# SCH_NFC-Card-Brendon_2024-10-28.net
KiCad netlist of a schematic drawn in EasyEDA
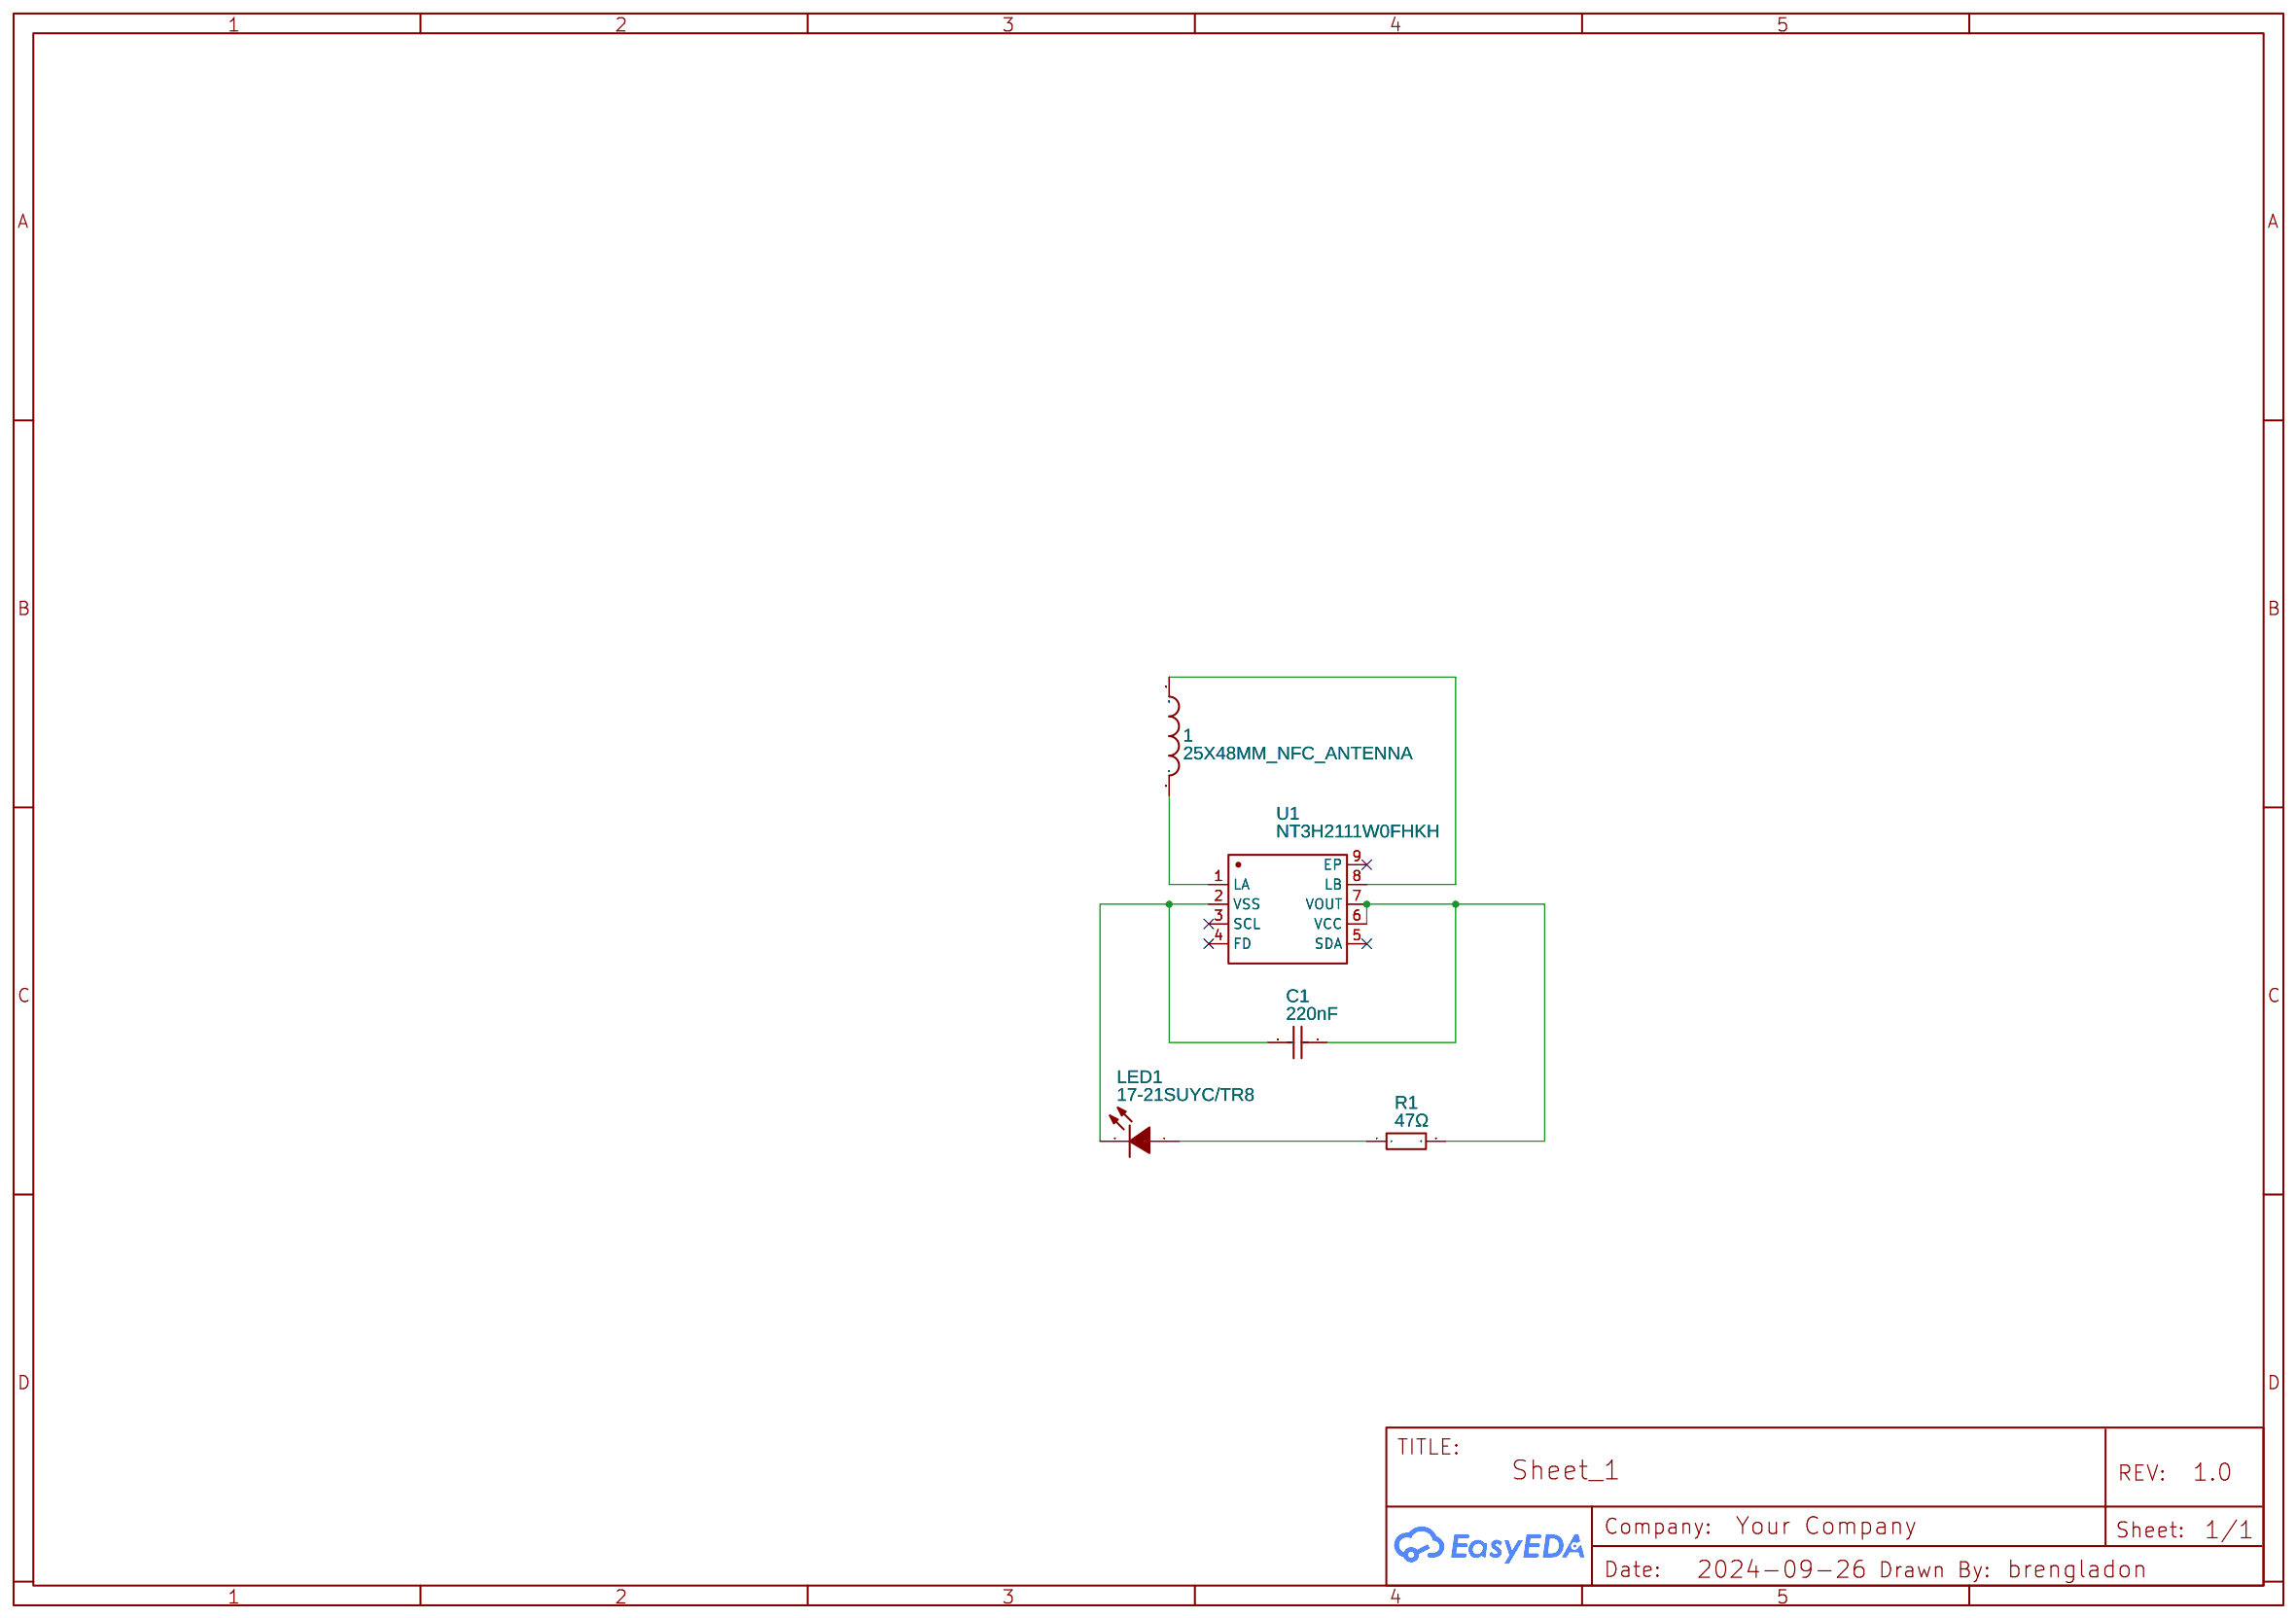
[diagram p0: schematic sheet]

(export (version "E")
  (design (tool "Eeschema 10.0.6"))
  (components
    (comp (ref "1") (value "25X48MM_NFC_ANTENNA") (libsource (lib "") (part "25X48MM_NFC_ANTENNA")))
    (comp (ref "C1")
      (value "220nF")
      (fields
        (field (name "Manufacturer Part") "CL10B224KA8NNNC")
        (field (name "Manufacturer") "SAMSUNG(三星)")
      )
      (libsource (lib "") (part "CL10B224KA8NNNC"))
    )
    (comp (ref "LED1")
      (value "17-21SUYC/TR8")
      (fields (field (name "Manufacturer Part") "KT-0805黄灯") (field (name "Manufacturer") "KENTO"))
      (libsource (lib "") (part "17-21SUYC/TR8"))
    )
    (comp (ref "R1")
      (value "47Ω")
      (fields
        (field (name "Manufacturer Part") "0603WAF470JT5E")
        (field (name "Manufacturer") "UNI-ROYAL(厚声)")
      )
      (libsource (lib "") (part "0603WAF470JT5E"))
    )
    (comp (ref "U1")
      (value "NT3H2111W0FHKH")
      (fields (field (name "Manufacturer") "NXP(恩智浦)"))
      (libsource (lib "") (part "NT3H2111W0FHKH"))
    )
  )
  (nets
    (net (code "1") (name "Net-(LED1-+)") (class "Default")
      (node (ref "LED1") (pin "1") (pinfunction "+_1") (pintype "unspecified"))
      (node (ref "R1") (pin "1") (pinfunction "1_1") (pintype "input"))
    )
    (net (code "2") (name "Net-(LED1--)") (class "Default")
      (node (ref "C1") (pin "1") (pinfunction "1_1") (pintype "input"))
      (node (ref "LED1") (pin "2") (pinfunction "-_2") (pintype "unspecified"))
      (node (ref "U1") (pin "2") (pinfunction "VSS_2") (pintype "unspecified"))
    )
    (net (code "3") (name "Net-(U1-LA)") (class "Default")
      (node (ref "1") (pin "P$2") (pinfunction "P$2_P$2") (pintype "bidirectional"))
      (node (ref "U1") (pin "1") (pinfunction "LA_1") (pintype "unspecified"))
    )
    (net (code "4") (name "Net-(U1-LB)") (class "Default")
      (node (ref "1") (pin "P$1") (pinfunction "P$1_P$1") (pintype "bidirectional"))
      (node (ref "U1") (pin "8") (pinfunction "LB_8") (pintype "unspecified"))
    )
    (net (code "5") (name "Net-(U1-VCC)") (class "Default")
      (node (ref "C1") (pin "2") (pinfunction "2_2") (pintype "input"))
      (node (ref "R1") (pin "2") (pinfunction "2_2") (pintype "input"))
      (node (ref "U1") (pin "6") (pinfunction "VCC_6") (pintype "unspecified"))
      (node (ref "U1") (pin "7") (pinfunction "VOUT_7") (pintype "unspecified"))
    )
    (net (code "6") (name "unconnected-(U1-EP-Pad9)") (class "Default")
      (node (ref "U1") (pin "9") (pinfunction "EP_9") (pintype "unspecified+no_connect"))
    )
    (net (code "7") (name "unconnected-(U1-FD-Pad4)") (class "Default")
      (node (ref "U1") (pin "4") (pinfunction "FD_4") (pintype "unspecified+no_connect"))
    )
    (net (code "8") (name "unconnected-(U1-SCL-Pad3)") (class "Default")
      (node (ref "U1") (pin "3") (pinfunction "SCL_3") (pintype "unspecified+no_connect"))
    )
    (net (code "9") (name "unconnected-(U1-SDA-Pad5)") (class "Default")
      (node (ref "U1") (pin "5") (pinfunction "SDA_5") (pintype "unspecified+no_connect"))
    )
  )
)
